# RTD.net
KiCad netlist of a schematic drawn in Altium Designer
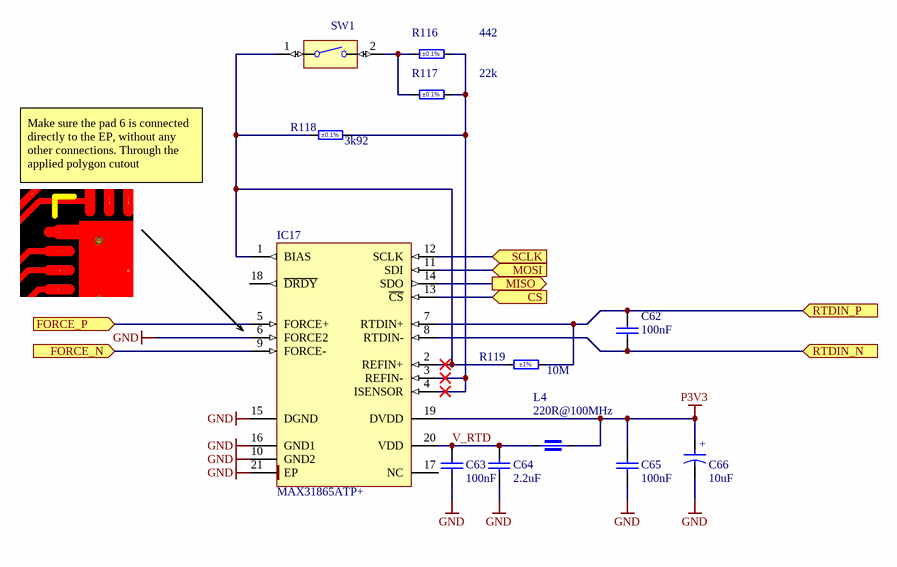
[diagram p0: RTD.SchDoc]

(export (version "E")
  (design (tool "Eeschema 10.0.6"))
  (components
    (comp (ref "C62")
      (value "100nF")
      (footprint "CAPC1608X87N")
      (description "Non-polarised capacitor")
      (fields
        (field (name "PART NUMBER") "CC0603_100NF_50V_10%_X7R")
        (field (name "VOLTAGE") "50V")
        (field (name "AUTHOR") "CERN DEM JLC")
      )
      (libsource (lib "Capacitors") (part "Capacitor - non polarized"))
    )
    (comp (ref "C63")
      (value "100nF")
      (footprint "CAPC1608X87N")
      (description "Non-polarised capacitor")
      (fields
        (field (name "PART NUMBER") "CC0603_100NF_50V_10%_X7R")
        (field (name "VOLTAGE") "50V")
        (field (name "AUTHOR") "CERN DEM JLC")
      )
      (libsource (lib "Capacitors") (part "Capacitor - non polarized"))
    )
    (comp (ref "C64")
      (value "2.2uF")
      (footprint "CAPC1608X90N")
      (description "Non-polarised capacitor")
      (fields
        (field (name "PART NUMBER") "CC0603_2.2UF_10V_20%_X7R")
        (field (name "VOLTAGE") "10V")
        (field (name "AUTHOR") "CERN DEM JLC")
      )
      (libsource (lib "Capacitors") (part "Capacitor - non polarized"))
    )
    (comp (ref "C65")
      (value "100nF")
      (footprint "CAPC1608X87N")
      (description "Non-polarised capacitor")
      (fields
        (field (name "PART NUMBER") "CC0603_100NF_50V_10%_X7R")
        (field (name "VOLTAGE") "50V")
        (field (name "AUTHOR") "CERN DEM JLC")
      )
      (libsource (lib "Capacitors") (part "Capacitor - non polarized"))
    )
    (comp (ref "C66")
      (value "10uF")
      (footprint "CAPMP3216X180N")
      (description "Polarised capacitor")
      (fields
        (field (name "PART NUMBER") "CTE3216-18_10UF_16V_20%_AVX_TCJ")
        (field (name "VOLTAGE") "16V")
        (field (name "AUTHOR") "CERN DEM JLC")
      )
      (libsource (lib "Capacitors") (part "Capacitor - polarized"))
    )
    (comp (ref "IC17")
      (value "MAX31865ATP+")
      (footprint "QFN65P500X500X80-21N-S335")
      (description "RTD-to-Digital Converter")
      (fields
        (field (name "MANUFACTURER") "MAXIM")
        (field (name "MANUFACTURER PART NUMBER") "MAX31865ATP")
        (field (name "AUTHOR") "CERN DEM MR")
      )
      (libsource (lib "ICs And Semiconductors") (part "MAX31865ATP+"))
    )
    (comp (ref "L4")
      (value "220R@100MHz")
      (footprint "INDC1608X95N")
      (fields
        (field (name "PART NUMBER") "IND0603_MURATA_BLM18SG221TN1")
        (field (name "POWER") "2.5A")
        (field (name "TOLERANCE") "±25%")
        (field (name "AUTHOR") "CERN DEM MR")
      )
      (libsource (lib "Inductors & Transformers") (part "Ferrite Bead"))
    )
    (comp (ref "R116")
      (value "442")
      (footprint "RESC1608X55N")
      (description "Resistor - 0.1%")
      (fields
        (field (name "TOLERANCE") "±0.1%")
        (field (name "PART NUMBER") "R0603_442R_0.1%_0.063W_10PPM")
        (field (name "POWER") "0.063W")
        (field (name "AUTHOR") "CERN DEM JLC")
      )
      (libsource (lib "Resistors") (part "Resistor - 0.1%"))
    )
    (comp (ref "R117")
      (value "22k")
      (footprint "RESC1608X64N")
      (description "Resistor - 0.1%")
      (fields
        (field (name "TOLERANCE") "±0.1%")
        (field (name "PART NUMBER") "R0603_22K_0.1%_0.1W_25PPM")
        (field (name "POWER") "0.1W")
        (field (name "AUTHOR") "CERN DEM HF")
      )
      (libsource (lib "Resistors") (part "Resistor - 0.1%"))
    )
    (comp (ref "R118")
      (value "3k92")
      (footprint "RESC1608X55N")
      (description "Resistor - 0.1%")
      (fields
        (field (name "TOLERANCE") "±0.1%")
        (field (name "PART NUMBER") "R0603_3K92_0.1%_0.063W_10PPM")
        (field (name "POWER") "0.063W")
        (field (name "AUTHOR") "CERN DEM JLC")
      )
      (libsource (lib "Resistors") (part "Resistor - 0.1%"))
    )
    (comp (ref "R119")
      (value "10M")
      (footprint "RESC1608X55N")
      (description "Resistor - 1%")
      (fields
        (field (name "TOLERANCE") "±1%")
        (field (name "PART NUMBER") "R0603_10M_1%_0.1W_100PPM")
        (field (name "POWER") "0.1W")
        (field (name "AUTHOR") "CERN DEM JLC")
      )
      (libsource (lib "Resistors") (part "Resistor - 1%"))
    )
    (comp (ref "SW1")
      (value "Switch")
      (footprint "SW_OMRON_A6SN-1101")
      (description "1 Ways SPST DIP Switch")
      (fields
        (field (name "PART NUMBER") "SW_OMRON_A6SN-1101")
        (field (name "MANUFACTURER") "OMRON")
        (field (name "AUTHOR") "CERN DEM JLC")
      )
      (libsource (lib "Eletro-mechanical") (part "SW 1x SPST DIP Switch"))
    )
  )
  (nets
    (net (code "1") (name "/CS") (class "Default")
      (node (ref "IC17") (pin "13") (pinfunction "~{CS}_13") (pintype "input"))
    )
    (net (code "2") (name "/FORCE_N") (class "Default")
      (node (ref "IC17") (pin "9") (pinfunction "FORCE-_9") (pintype "input"))
    )
    (net (code "3") (name "/FORCE_P") (class "Default")
      (node (ref "IC17") (pin "5") (pinfunction "FORCE+_5") (pintype "input"))
    )
    (net (code "4") (name "/MISO") (class "Default")
      (node (ref "IC17") (pin "14") (pinfunction "SDO_14") (pintype "output"))
    )
    (net (code "5") (name "/MOSI") (class "Default")
      (node (ref "IC17") (pin "11") (pinfunction "SDI_11") (pintype "input"))
    )
    (net (code "6") (name "/RTDIN_N") (class "Default")
      (node (ref "C62") (pin "1") (pinfunction "1_1") (pintype "passive"))
      (node (ref "IC17") (pin "8") (pinfunction "RTDIN-_8") (pintype "input"))
    )
    (net (code "7") (name "/RTDIN_P") (class "Default")
      (node (ref "C62") (pin "2") (pinfunction "2_2") (pintype "passive"))
      (node (ref "IC17") (pin "7") (pinfunction "RTDIN+_7") (pintype "input"))
      (node (ref "R119") (pin "2") (pinfunction "2_2") (pintype "passive"))
    )
    (net (code "8") (name "/SCLK") (class "Default")
      (node (ref "IC17") (pin "12") (pinfunction "SCLK_12") (pintype "input"))
    )
    (net (code "9") (name "/V_RTD") (class "Default")
      (node (ref "C63") (pin "2") (pinfunction "2_2") (pintype "passive"))
      (node (ref "C64") (pin "2") (pinfunction "2_2") (pintype "passive"))
      (node (ref "IC17") (pin "20") (pinfunction "VDD_20") (pintype "power_in"))
      (node (ref "L4") (pin "1") (pinfunction "1_1") (pintype "passive"))
    )
    (net (code "10") (name "GND") (class "Default")
      (node (ref "C63") (pin "1") (pinfunction "1_1") (pintype "passive"))
      (node (ref "C64") (pin "1") (pinfunction "1_1") (pintype "passive"))
      (node (ref "C65") (pin "1") (pinfunction "1_1") (pintype "passive"))
      (node (ref "C66") (pin "2") (pinfunction "2_2") (pintype "passive"))
      (node (ref "IC17") (pin "10") (pinfunction "GND2_10") (pintype "power_in"))
      (node (ref "IC17") (pin "15") (pinfunction "DGND_15") (pintype "power_in"))
      (node (ref "IC17") (pin "16") (pinfunction "GND1_16") (pintype "power_in"))
      (node (ref "IC17") (pin "21") (pinfunction "EP_21") (pintype "power_in"))
      (node (ref "IC17") (pin "6") (pinfunction "FORCE2_6") (pintype "input"))
    )
    (net (code "11") (name "Net-(IC17-BIAS)") (class "Default")
      (node (ref "IC17") (pin "1") (pinfunction "BIAS_1") (pintype "output"))
      (node (ref "IC17") (pin "2") (pinfunction "REFIN+_2") (pintype "input"))
      (node (ref "R118") (pin "1") (pinfunction "1_1") (pintype "passive"))
      (node (ref "R119") (pin "1") (pinfunction "1_1") (pintype "passive"))
      (node (ref "SW1") (pin "1") (pinfunction "1_1") (pintype "bidirectional"))
    )
    (net (code "12") (name "Net-(IC17-ISENSOR)") (class "Default")
      (node (ref "IC17") (pin "3") (pinfunction "REFIN-_3") (pintype "input"))
      (node (ref "IC17") (pin "4") (pinfunction "ISENSOR_4") (pintype "input"))
      (node (ref "R116") (pin "2") (pinfunction "2_2") (pintype "passive"))
      (node (ref "R117") (pin "2") (pinfunction "2_2") (pintype "passive"))
      (node (ref "R118") (pin "2") (pinfunction "2_2") (pintype "passive"))
    )
    (net (code "13") (name "Net-(R116-Pad1)") (class "Default")
      (node (ref "R116") (pin "1") (pinfunction "1_1") (pintype "passive"))
      (node (ref "R117") (pin "1") (pinfunction "1_1") (pintype "passive"))
      (node (ref "SW1") (pin "2") (pinfunction "2_2") (pintype "bidirectional"))
    )
    (net (code "14") (name "P3V3") (class "Default")
      (node (ref "C65") (pin "2") (pinfunction "2_2") (pintype "passive"))
      (node (ref "C66") (pin "1") (pinfunction "1_1") (pintype "passive"))
      (node (ref "IC17") (pin "19") (pinfunction "DVDD_19") (pintype "power_in"))
      (node (ref "L4") (pin "2") (pinfunction "2_2") (pintype "passive"))
    )
    (net (code "15") (name "unconnected-(IC17-NC-Pad17)") (class "Default")
      (node (ref "IC17") (pin "17") (pinfunction "NC_17") (pintype "passive"))
    )
    (net (code "16") (name "unconnected-(IC17-~{DRDY}-Pad18)") (class "Default")
      (node (ref "IC17") (pin "18") (pinfunction "~{DRDY}_18") (pintype "output"))
    )
  )
)
